# USBFX2LP_3.net
KiCad netlist of a schematic drawn in Altium Designer
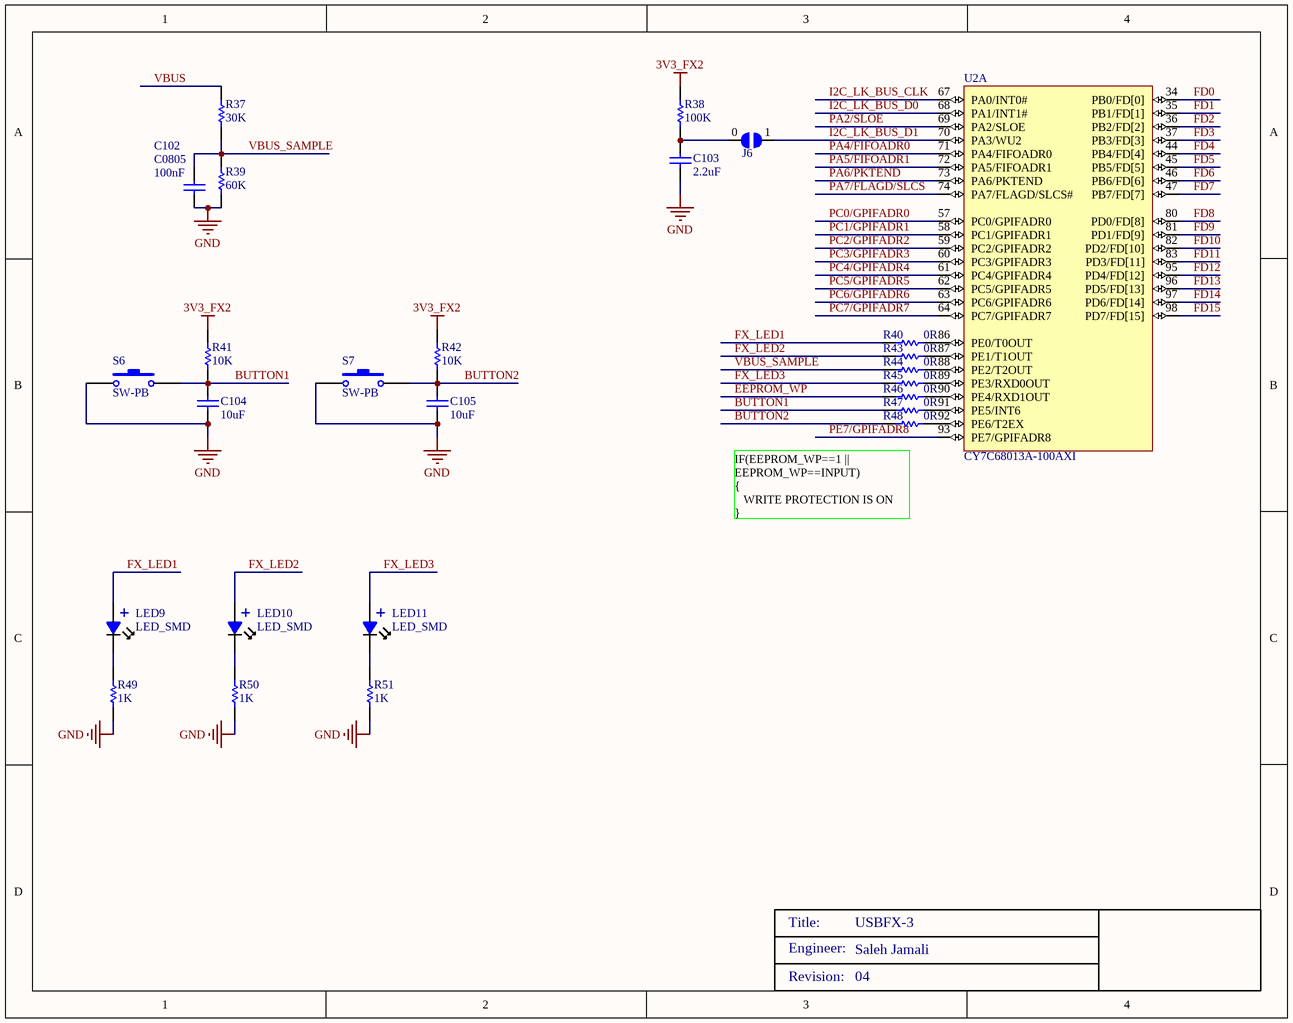
[diagram p0: USBFX2LP_3.SchDoc]

(export (version "E")
  (design (tool "Eeschema 10.0.6"))
  (components
    (comp (ref "C102")
      (value "C0805")
      (footprint "0805")
      (description "Ceramic Chip Capacitor - Standard")
      (fields (field (name "ALTIUM_VALUE") "100nF") (field (name "PUBLISHER") "Altium Limited"))
      (libsource (lib "KEMET Chip Capacitor") (part "C0805"))
    )
    (comp (ref "C103")
      (value "2.2uF")
      (footprint "0805")
      (description "Ceramic Chip Capacitor - Standard")
      (fields (field (name "Comment") "C0805") (field (name "PUBLISHER") "Altium Limited"))
      (libsource (lib "KEMET Chip Capacitor") (part "C0805"))
    )
    (comp (ref "C104")
      (value "10uF")
      (footprint "0805")
      (description "Ceramic Chip Capacitor - Standard")
      (fields (field (name "Comment") "C0805") (field (name "PUBLISHER") "Altium Limited"))
      (libsource (lib "KEMET Chip Capacitor") (part "C0805"))
    )
    (comp (ref "C105")
      (value "10uF")
      (footprint "0805")
      (description "Ceramic Chip Capacitor - Standard")
      (fields (field (name "Comment") "C0805") (field (name "PUBLISHER") "Altium Limited"))
      (libsource (lib "KEMET Chip Capacitor") (part "C0805"))
    )
    (comp (ref "J6")
      (value "jumper")
      (footprint "jumper_pcb")
      (libsource (lib "JUMPPER_PRJ") (part "jumper"))
    )
    (comp (ref "LED9") (value "LED_SMD") (footprint "LED_805") (libsource (lib "LED_PRJCT") (part "LED_SMD")))
    (comp (ref "LED10")
      (value "LED_SMD")
      (footprint "LED_805")
      (libsource (lib "LED_PRJCT") (part "LED_SMD"))
    )
    (comp (ref "LED11")
      (value "LED_SMD")
      (footprint "LED_805")
      (libsource (lib "LED_PRJCT") (part "LED_SMD"))
    )
    (comp (ref "R37")
      (value "30K")
      (footprint "ERA-0805")
      (fields (field (name "PUBLISHER") "Altium Limited"))
      (libsource (lib "Panasonic Resistor") (part "ERA6Y"))
    )
    (comp (ref "R38")
      (value "100K")
      (footprint "ERA-0805")
      (fields (field (name "PUBLISHER") "Altium Limited"))
      (libsource (lib "Panasonic Resistor") (part "ERA6Y"))
    )
    (comp (ref "R39")
      (value "60K")
      (footprint "ERA-0805")
      (fields (field (name "PUBLISHER") "Altium Limited"))
      (libsource (lib "Panasonic Resistor") (part "ERA6Y"))
    )
    (comp (ref "R40")
      (value "0R")
      (footprint "ERA-0805")
      (fields (field (name "PUBLISHER") "Altium Limited"))
      (libsource (lib "Panasonic Resistor") (part "ERA6Y"))
    )
    (comp (ref "R41")
      (value "10K")
      (footprint "ERA-0805")
      (fields (field (name "PUBLISHER") "Altium Limited"))
      (libsource (lib "Panasonic Resistor") (part "ERA6Y"))
    )
    (comp (ref "R42")
      (value "10K")
      (footprint "ERA-0805")
      (fields (field (name "PUBLISHER") "Altium Limited"))
      (libsource (lib "Panasonic Resistor") (part "ERA6Y"))
    )
    (comp (ref "R43")
      (value "0R")
      (footprint "ERA-0805")
      (fields (field (name "PUBLISHER") "Altium Limited"))
      (libsource (lib "Panasonic Resistor") (part "ERA6Y"))
    )
    (comp (ref "R44")
      (value "0R")
      (footprint "ERA-0805")
      (fields (field (name "PUBLISHER") "Altium Limited"))
      (libsource (lib "Panasonic Resistor") (part "ERA6Y"))
    )
    (comp (ref "R45")
      (value "0R")
      (footprint "ERA-0805")
      (fields (field (name "PUBLISHER") "Altium Limited"))
      (libsource (lib "Panasonic Resistor") (part "ERA6Y"))
    )
    (comp (ref "R46")
      (value "0R")
      (footprint "ERA-0805")
      (fields (field (name "PUBLISHER") "Altium Limited"))
      (libsource (lib "Panasonic Resistor") (part "ERA6Y"))
    )
    (comp (ref "R47")
      (value "0R")
      (footprint "ERA-0805")
      (fields (field (name "PUBLISHER") "Altium Limited"))
      (libsource (lib "Panasonic Resistor") (part "ERA6Y"))
    )
    (comp (ref "R48")
      (value "0R")
      (footprint "ERA-0805")
      (fields (field (name "PUBLISHER") "Altium Limited"))
      (libsource (lib "Panasonic Resistor") (part "ERA6Y"))
    )
    (comp (ref "R49")
      (value "1K")
      (footprint "ERA-0805")
      (fields (field (name "PUBLISHER") "Altium Limited"))
      (libsource (lib "Panasonic Resistor") (part "ERA6Y"))
    )
    (comp (ref "R50")
      (value "1K")
      (footprint "ERA-0805")
      (fields (field (name "PUBLISHER") "Altium Limited"))
      (libsource (lib "Panasonic Resistor") (part "ERA6Y"))
    )
    (comp (ref "R51")
      (value "1K")
      (footprint "ERA-0805")
      (fields (field (name "PUBLISHER") "Altium Limited"))
      (libsource (lib "Panasonic Resistor") (part "ERA6Y"))
    )
    (comp (ref "S6")
      (value "SW-PB")
      (footprint "SPST-2")
      (description "Switch")
      (fields (field (name "PUBLISHER") "Altium Limited"))
      (libsource (lib "Miscellaneous Devices") (part "SW-PB"))
    )
    (comp (ref "S7")
      (value "SW-PB")
      (footprint "SPST-2")
      (description "Switch")
      (fields (field (name "PUBLISHER") "Altium Limited"))
      (libsource (lib "Miscellaneous Devices") (part "SW-PB"))
    )
    (comp (ref "U2")
      (value "CY7C68013A-100AXI")
      (footprint "CYP-AX100RA_N")
      (fields (field (name "MANUFACTURER") "Cypress"))
      (libsource (lib "Cypress USB Controllers") (part "CY7C68013A-100AXI"))
    )
  )
  (nets
    (net (code "1") (name "/BUTTON1") (class "Default")
      (node (ref "C104") (pin "2") (pinfunction "2_2") (pintype "passive"))
      (node (ref "R41") (pin "2") (pinfunction "2_2") (pintype "passive"))
      (node (ref "R47") (pin "1") (pinfunction "1_1") (pintype "passive"))
      (node (ref "S6") (pin "2") (pinfunction "2_2") (pintype "passive"))
    )
    (net (code "2") (name "/BUTTON2") (class "Default")
      (node (ref "C105") (pin "2") (pinfunction "2_2") (pintype "passive"))
      (node (ref "R42") (pin "2") (pinfunction "2_2") (pintype "passive"))
      (node (ref "R48") (pin "1") (pinfunction "1_1") (pintype "passive"))
      (node (ref "S7") (pin "2") (pinfunction "2_2") (pintype "passive"))
    )
    (net (code "3") (name "/EEPROM_WP") (class "Default")
      (node (ref "R46") (pin "1") (pinfunction "1_1") (pintype "passive"))
    )
    (net (code "4") (name "/FD0") (class "Default")
      (node (ref "U2") (pin "34") (pinfunction "PB0/FD[0]_34") (pintype "bidirectional"))
    )
    (net (code "5") (name "/FD1") (class "Default")
      (node (ref "U2") (pin "35") (pinfunction "PB1/FD[1]_35") (pintype "bidirectional"))
    )
    (net (code "6") (name "/FD2") (class "Default")
      (node (ref "U2") (pin "36") (pinfunction "PB2/FD[2]_36") (pintype "bidirectional"))
    )
    (net (code "7") (name "/FD3") (class "Default")
      (node (ref "U2") (pin "37") (pinfunction "PB3/FD[3]_37") (pintype "bidirectional"))
    )
    (net (code "8") (name "/FD4") (class "Default")
      (node (ref "U2") (pin "44") (pinfunction "PB4/FD[4]_44") (pintype "bidirectional"))
    )
    (net (code "9") (name "/FD5") (class "Default")
      (node (ref "U2") (pin "45") (pinfunction "PB5/FD[5]_45") (pintype "bidirectional"))
    )
    (net (code "10") (name "/FD6") (class "Default")
      (node (ref "U2") (pin "46") (pinfunction "PB6/FD[6]_46") (pintype "bidirectional"))
    )
    (net (code "11") (name "/FD7") (class "Default")
      (node (ref "U2") (pin "47") (pinfunction "PB7/FD[7]_47") (pintype "bidirectional"))
    )
    (net (code "12") (name "/FD8") (class "Default")
      (node (ref "U2") (pin "80") (pinfunction "PD0/FD[8]_80") (pintype "bidirectional"))
    )
    (net (code "13") (name "/FD9") (class "Default")
      (node (ref "U2") (pin "81") (pinfunction "PD1/FD[9]_81") (pintype "bidirectional"))
    )
    (net (code "14") (name "/FD10") (class "Default")
      (node (ref "U2") (pin "82") (pinfunction "PD2/FD[10]_82") (pintype "bidirectional"))
    )
    (net (code "15") (name "/FD11") (class "Default")
      (node (ref "U2") (pin "83") (pinfunction "PD3/FD[11]_83") (pintype "bidirectional"))
    )
    (net (code "16") (name "/FD12") (class "Default")
      (node (ref "U2") (pin "95") (pinfunction "PD4/FD[12]_95") (pintype "bidirectional"))
    )
    (net (code "17") (name "/FD13") (class "Default")
      (node (ref "U2") (pin "96") (pinfunction "PD5/FD[13]_96") (pintype "bidirectional"))
    )
    (net (code "18") (name "/FD14") (class "Default")
      (node (ref "U2") (pin "97") (pinfunction "PD6/FD[14]_97") (pintype "bidirectional"))
    )
    (net (code "19") (name "/FD15") (class "Default")
      (node (ref "U2") (pin "98") (pinfunction "PD7/FD[15]_98") (pintype "bidirectional"))
    )
    (net (code "20") (name "/FX_LED1") (class "Default")
      (node (ref "LED9") (pin "1") (pinfunction "1_1") (pintype "passive"))
      (node (ref "R40") (pin "1") (pinfunction "1_1") (pintype "passive"))
    )
    (net (code "21") (name "/FX_LED2") (class "Default")
      (node (ref "LED10") (pin "1") (pinfunction "1_1") (pintype "passive"))
      (node (ref "R43") (pin "1") (pinfunction "1_1") (pintype "passive"))
    )
    (net (code "22") (name "/FX_LED3") (class "Default")
      (node (ref "LED11") (pin "1") (pinfunction "1_1") (pintype "passive"))
      (node (ref "R45") (pin "1") (pinfunction "1_1") (pintype "passive"))
    )
    (net (code "23") (name "/I2C_LK_BUS_CLK") (class "Default")
      (node (ref "U2") (pin "67") (pinfunction "PA0/INT0#_67") (pintype "bidirectional"))
    )
    (net (code "24") (name "/I2C_LK_BUS_D0") (class "Default")
      (node (ref "U2") (pin "68") (pinfunction "PA1/INT1#_68") (pintype "bidirectional"))
    )
    (net (code "25") (name "/I2C_LK_BUS_D1") (class "Default")
      (node (ref "J6") (pin "1") (pintype "passive"))
      (node (ref "U2") (pin "70") (pinfunction "PA3/WU2_70") (pintype "bidirectional"))
    )
    (net (code "26") (name "/PA2{slash}SLOE") (class "Default")
      (node (ref "U2") (pin "69") (pinfunction "PA2/SLOE_69") (pintype "bidirectional"))
    )
    (net (code "27") (name "/PA4{slash}FIFOADR0") (class "Default")
      (node (ref "U2") (pin "71") (pinfunction "PA4/FIFOADR0_71") (pintype "bidirectional"))
    )
    (net (code "28") (name "/PA5{slash}FIFOADR1") (class "Default")
      (node (ref "U2") (pin "72") (pinfunction "PA5/FIFOADR1_72") (pintype "bidirectional"))
    )
    (net (code "29") (name "/PA6{slash}PKTEND") (class "Default")
      (node (ref "U2") (pin "73") (pinfunction "PA6/PKTEND_73") (pintype "bidirectional"))
    )
    (net (code "30") (name "/PA7{slash}FLAGD{slash}SLCS") (class "Default")
      (node (ref "U2") (pin "74") (pinfunction "PA7/FLAGD/SLCS#_74") (pintype "bidirectional"))
    )
    (net (code "31") (name "/PC0{slash}GPIFADR0") (class "Default")
      (node (ref "U2") (pin "57") (pinfunction "PC0/GPIFADR0_57") (pintype "bidirectional"))
    )
    (net (code "32") (name "/PC1{slash}GPIFADR1") (class "Default")
      (node (ref "U2") (pin "58") (pinfunction "PC1/GPIFADR1_58") (pintype "bidirectional"))
    )
    (net (code "33") (name "/PC2{slash}GPIFADR2") (class "Default")
      (node (ref "U2") (pin "59") (pinfunction "PC2/GPIFADR2_59") (pintype "bidirectional"))
    )
    (net (code "34") (name "/PC3{slash}GPIFADR3") (class "Default")
      (node (ref "U2") (pin "60") (pinfunction "PC3/GPIFADR3_60") (pintype "bidirectional"))
    )
    (net (code "35") (name "/PC4{slash}GPIFADR4") (class "Default")
      (node (ref "U2") (pin "61") (pinfunction "PC4/GPIFADR4_61") (pintype "bidirectional"))
    )
    (net (code "36") (name "/PC5{slash}GPIFADR5") (class "Default")
      (node (ref "U2") (pin "62") (pinfunction "PC5/GPIFADR5_62") (pintype "bidirectional"))
    )
    (net (code "37") (name "/PC6{slash}GPIFADR6") (class "Default")
      (node (ref "U2") (pin "63") (pinfunction "PC6/GPIFADR6_63") (pintype "bidirectional"))
    )
    (net (code "38") (name "/PC7{slash}GPIFADR7") (class "Default")
      (node (ref "U2") (pin "64") (pinfunction "PC7/GPIFADR7_64") (pintype "bidirectional"))
    )
    (net (code "39") (name "/PE7{slash}GPIFADR8") (class "Default")
      (node (ref "U2") (pin "93") (pinfunction "PE7/GPIFADR8_93") (pintype "bidirectional"))
    )
    (net (code "40") (name "/VBUS") (class "Default")
      (node (ref "R37") (pin "1") (pinfunction "1_1") (pintype "passive"))
    )
    (net (code "41") (name "/VBUS_SAMPLE") (class "Default")
      (node (ref "C102") (pin "2") (pinfunction "2_2") (pintype "passive"))
      (node (ref "R37") (pin "2") (pinfunction "2_2") (pintype "passive"))
      (node (ref "R39") (pin "1") (pinfunction "1_1") (pintype "passive"))
      (node (ref "R44") (pin "1") (pinfunction "1_1") (pintype "passive"))
    )
    (net (code "42") (name "3V3_FX2") (class "Default")
      (node (ref "R38") (pin "1") (pinfunction "1_1") (pintype "passive"))
      (node (ref "R41") (pin "1") (pinfunction "1_1") (pintype "passive"))
      (node (ref "R42") (pin "1") (pinfunction "1_1") (pintype "passive"))
    )
    (net (code "43") (name "GND") (class "Default")
      (node (ref "C102") (pin "1") (pinfunction "1_1") (pintype "passive"))
      (node (ref "C103") (pin "1") (pinfunction "1_1") (pintype "passive"))
      (node (ref "C104") (pin "1") (pinfunction "1_1") (pintype "passive"))
      (node (ref "C105") (pin "1") (pinfunction "1_1") (pintype "passive"))
      (node (ref "R39") (pin "2") (pinfunction "2_2") (pintype "passive"))
      (node (ref "R49") (pin "1") (pinfunction "1_1") (pintype "passive"))
      (node (ref "R50") (pin "1") (pinfunction "1_1") (pintype "passive"))
      (node (ref "R51") (pin "1") (pinfunction "1_1") (pintype "passive"))
      (node (ref "S6") (pin "1") (pinfunction "1_1") (pintype "passive"))
      (node (ref "S7") (pin "1") (pinfunction "1_1") (pintype "passive"))
    )
    (net (code "44") (name "Net-(C103-Pad2)") (class "Default")
      (node (ref "C103") (pin "2") (pinfunction "2_2") (pintype "passive"))
      (node (ref "J6") (pin "0") (pintype "passive"))
      (node (ref "R38") (pin "2") (pinfunction "2_2") (pintype "passive"))
    )
    (net (code "45") (name "Net-(LED9-Pad2)") (class "Default")
      (node (ref "LED9") (pin "2") (pinfunction "2_2") (pintype "passive"))
      (node (ref "R49") (pin "2") (pinfunction "2_2") (pintype "passive"))
    )
    (net (code "46") (name "Net-(LED10-Pad2)") (class "Default")
      (node (ref "LED10") (pin "2") (pinfunction "2_2") (pintype "passive"))
      (node (ref "R50") (pin "2") (pinfunction "2_2") (pintype "passive"))
    )
    (net (code "47") (name "Net-(LED11-Pad2)") (class "Default")
      (node (ref "LED11") (pin "2") (pinfunction "2_2") (pintype "passive"))
      (node (ref "R51") (pin "2") (pinfunction "2_2") (pintype "passive"))
    )
    (net (code "48") (name "Net-(U2A-PE0{slash}T0OUT)") (class "Default")
      (node (ref "R40") (pin "2") (pinfunction "2_2") (pintype "passive"))
      (node (ref "U2") (pin "86") (pinfunction "PE0/T0OUT_86") (pintype "bidirectional"))
    )
    (net (code "49") (name "Net-(U2A-PE1{slash}T1OUT)") (class "Default")
      (node (ref "R43") (pin "2") (pinfunction "2_2") (pintype "passive"))
      (node (ref "U2") (pin "87") (pinfunction "PE1/T1OUT_87") (pintype "bidirectional"))
    )
    (net (code "50") (name "Net-(U2A-PE2{slash}T2OUT)") (class "Default")
      (node (ref "R44") (pin "2") (pinfunction "2_2") (pintype "passive"))
      (node (ref "U2") (pin "88") (pinfunction "PE2/T2OUT_88") (pintype "bidirectional"))
    )
    (net (code "51") (name "Net-(U2A-PE3{slash}RXD0OUT)") (class "Default")
      (node (ref "R45") (pin "2") (pinfunction "2_2") (pintype "passive"))
      (node (ref "U2") (pin "89") (pinfunction "PE3/RXD0OUT_89") (pintype "bidirectional"))
    )
    (net (code "52") (name "Net-(U2A-PE4{slash}RXD1OUT)") (class "Default")
      (node (ref "R46") (pin "2") (pinfunction "2_2") (pintype "passive"))
      (node (ref "U2") (pin "90") (pinfunction "PE4/RXD1OUT_90") (pintype "bidirectional"))
    )
    (net (code "53") (name "Net-(U2A-PE5{slash}INT6)") (class "Default")
      (node (ref "R47") (pin "2") (pinfunction "2_2") (pintype "passive"))
      (node (ref "U2") (pin "91") (pinfunction "PE5/INT6_91") (pintype "bidirectional"))
    )
    (net (code "54") (name "Net-(U2A-PE6{slash}T2EX)") (class "Default")
      (node (ref "R48") (pin "2") (pinfunction "2_2") (pintype "passive"))
      (node (ref "U2") (pin "92") (pinfunction "PE6/T2EX_92") (pintype "bidirectional"))
    )
  )
)
